# NPZ.net
KiCad netlist of a schematic drawn in Altium Designer
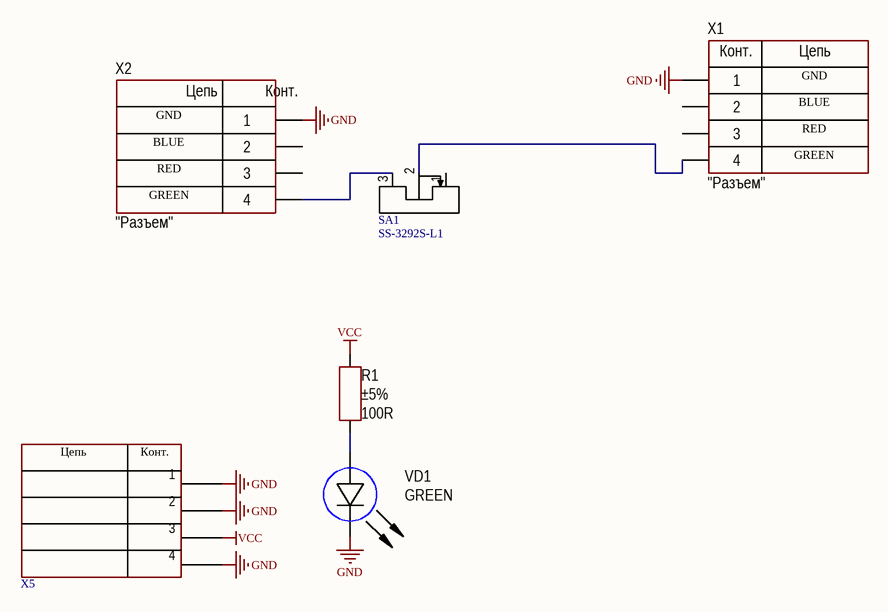
[diagram p0: NPZ.SchDoc]

(export (version "E")
  (design (tool "Eeschema 10.0.6"))
  (components
    (comp (ref "R1")
      (value "100R")
      (footprint "RES: 0603")
      (fields
        (field (name "MANUFACTURER") "Yageo")
        (field (name "PARTNUMBER") "RC0603JR-07100RL")
        (field (name "VALUEMANUFACTURERPARTNUMBER") "Resistor film, 100R, ±5%, 0603, 0.1W, -55...+125°C")
        (field (name "TOLERANCE") "±5%")
      )
      (libsource (lib "Resistor") (part "Resistor_0603"))
    )
    (comp (ref "SA1")
      (value "SS-3292S-L1")
      (footprint "SS-3292S-L1")
      (libsource (lib "switch") (part "SS-3292S-L1"))
    )
    (comp (ref "VD1")
      (value "~")
      (footprint "LED: 0805G")
      (fields
        (field (name "VALUEMANUFACTURERPARTNUMBER") "LED, *, *, *, -55...+150°C")
        (field (name "COLOR") "GREEN")
      )
      (libsource (lib "Diode") (part "LED_single"))
    )
    (comp (ref "X1")
      (value "~")
      (footprint "4PLS RIGHT ANGLE 2")
      (fields
        (field (name "MANUFACTURER") "Connfly")
        (field (name "VALUEMANUFACTURERPARTNUMBER") "Connector, 4pin, 2.54mm, 500VAC, 3A")
        (field (name "PARTNUMBER") "PLS-4")
        (field (name "COMMENTTEXT") "\"Разъем\"")
      )
      (libsource (lib "Connector") (part "PLS-4"))
    )
    (comp (ref "X2")
      (value "~")
      (footprint "CON: PBS-4 R")
      (fields
        (field (name "MANUFACTURER") "Connfly")
        (field (name "VALUEMANUFACTURERPARTNUMBER") "Connector, 4pin, 2.54mm, 500VAC, 3A")
        (field (name "PARTNUMBER") "PBS-4")
        (field (name "COMMENTTEXT") "\"Разъем\"")
      )
      (libsource (lib "Connector") (part "PBS-4"))
    )
    (comp (ref "X5")
      (value "PBS-4 cut")
      (footprint "PBS-4 CUT")
      (libsource (lib "conect") (part "PBS-4 cut"))
    )
  )
  (nets
    (net (code "1") (name "GND") (class "Default")
      (node (ref "VD1") (pin "2") (pinfunction "C_2") (pintype "passive"))
      (node (ref "X1") (pin "1") (pinfunction "1_1") (pintype "passive"))
      (node (ref "X2") (pin "1") (pinfunction "1_1") (pintype "passive"))
      (node (ref "X5") (pin "1") (pinfunction "1_1") (pintype "passive"))
      (node (ref "X5") (pin "2") (pinfunction "2_2") (pintype "passive"))
      (node (ref "X5") (pin "4") (pinfunction "4_4") (pintype "passive"))
    )
    (net (code "2") (name "Net-(SA1-Pad2)") (class "Default")
      (node (ref "SA1") (pin "2") (pinfunction "2_2") (pintype "passive"))
      (node (ref "X1") (pin "4") (pinfunction "4_4") (pintype "power_in"))
    )
    (net (code "3") (name "Net-(SA1-Pad3)") (class "Default")
      (node (ref "SA1") (pin "3") (pinfunction "3_3") (pintype "passive"))
      (node (ref "X2") (pin "4") (pinfunction "4_4") (pintype "power_in"))
    )
    (net (code "4") (name "Net-(VD1-A)") (class "Default")
      (node (ref "R1") (pin "1") (pinfunction "1_1") (pintype "passive"))
      (node (ref "VD1") (pin "1") (pinfunction "A_1") (pintype "passive"))
    )
    (net (code "5") (name "VCC") (class "Default")
      (node (ref "R1") (pin "2") (pinfunction "2_2") (pintype "passive"))
      (node (ref "X5") (pin "3") (pinfunction "3_3") (pintype "passive"))
    )
    (net (code "6") (name "unconnected-(SA1-Pad1)") (class "Default")
      (node (ref "SA1") (pin "1") (pinfunction "1_1") (pintype "passive"))
    )
    (net (code "7") (name "unconnected-(X1-Pad2)") (class "Default")
      (node (ref "X1") (pin "2") (pinfunction "2_2") (pintype "passive"))
    )
    (net (code "8") (name "unconnected-(X1-Pad3)") (class "Default")
      (node (ref "X1") (pin "3") (pinfunction "3_3") (pintype "power_in"))
    )
    (net (code "9") (name "unconnected-(X2-Pad2)") (class "Default")
      (node (ref "X2") (pin "2") (pinfunction "2_2") (pintype "passive"))
    )
    (net (code "10") (name "unconnected-(X2-Pad3)") (class "Default")
      (node (ref "X2") (pin "3") (pinfunction "3_3") (pintype "power_in"))
    )
  )
)
